# Board1.net
KiCad netlist of a schematic drawn in EAGLE
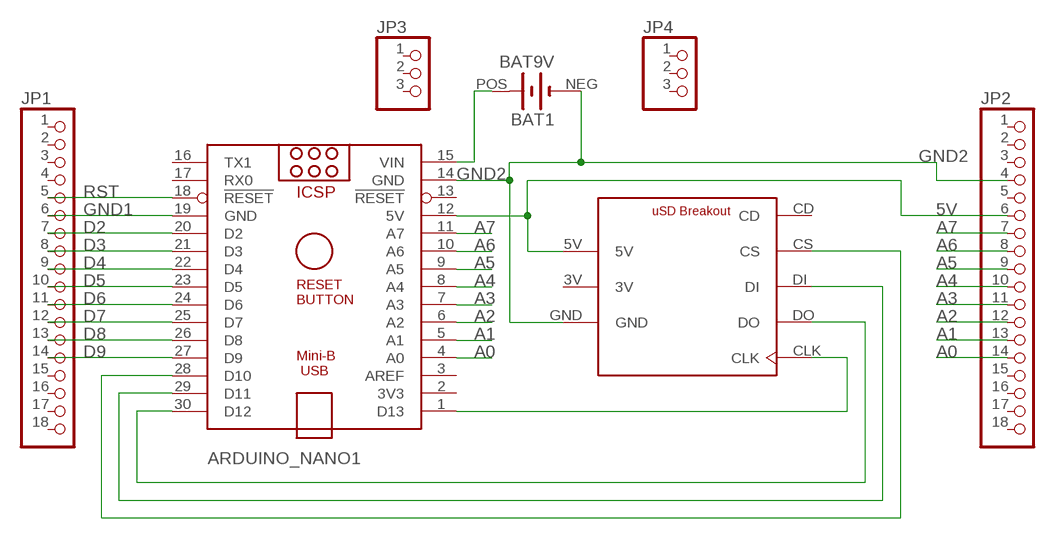
[diagram p0: schematic, sheet 1]

(export (version "E")
  (design (tool "Eeschema 10.0.6"))
  (components
    (comp (ref "ARDUINO_NANO1")
      (value "ARDUINO_NANO")
      (footprint "eagle-import:ARDUINO_NANO")
      (libsource (lib "eagle-import") (part "ARDUINO_NANO"))
    )
    (comp (ref "BAT1")
      (value "BAT9V")
      (footprint "eagle-import:BAT9V")
      (libsource (lib "eagle-import") (part "BAT9V"))
    )
    (comp (ref "JP1")
      (value "PINHD-1X18")
      (footprint "eagle-import:1X18")
      (libsource (lib "eagle-import") (part "PINHD-1X18"))
    )
    (comp (ref "JP2")
      (value "PINHD-1X18")
      (footprint "eagle-import:1X18")
      (libsource (lib "eagle-import") (part "PINHD-1X18"))
    )
    (comp (ref "JP3")
      (value "PINHD-1X3")
      (footprint "eagle-import:1X03")
      (libsource (lib "eagle-import") (part "PINHD-1X3"))
    )
    (comp (ref "JP4")
      (value "PINHD-1X3")
      (footprint "eagle-import:1X03")
      (libsource (lib "eagle-import") (part "PINHD-1X3"))
    )
    (comp (ref "USD1")
      (value "ADA254")
      (footprint "eagle-import:ADA254")
      (libsource (lib "eagle-import") (part "ADA254"))
    )
  )
  (nets
    (net (code "1") (name "/5V") (class "Default")
      (node (ref "ARDUINO_NANO1") (pin "12") (pinfunction "5V_12") (pintype "power_in"))
      (node (ref "JP2") (pin "6") (pinfunction "6_6") (pintype "passive"))
      (node (ref "USD1") (pin "5V") (pinfunction "5V_5V") (pintype "power_in"))
    )
    (net (code "2") (name "/A0") (class "Default")
      (node (ref "ARDUINO_NANO1") (pin "4") (pinfunction "A0_4") (pintype "bidirectional"))
      (node (ref "JP2") (pin "14") (pinfunction "14_14") (pintype "passive"))
    )
    (net (code "3") (name "/A1") (class "Default")
      (node (ref "ARDUINO_NANO1") (pin "5") (pinfunction "A1_5") (pintype "bidirectional"))
      (node (ref "JP2") (pin "13") (pinfunction "13_13") (pintype "passive"))
    )
    (net (code "4") (name "/A2") (class "Default")
      (node (ref "ARDUINO_NANO1") (pin "6") (pinfunction "A2_6") (pintype "bidirectional"))
      (node (ref "JP2") (pin "12") (pinfunction "12_12") (pintype "passive"))
    )
    (net (code "5") (name "/A3") (class "Default")
      (node (ref "ARDUINO_NANO1") (pin "7") (pinfunction "A3_7") (pintype "bidirectional"))
      (node (ref "JP2") (pin "11") (pinfunction "11_11") (pintype "passive"))
    )
    (net (code "6") (name "/A4") (class "Default")
      (node (ref "ARDUINO_NANO1") (pin "8") (pinfunction "A4_8") (pintype "bidirectional"))
      (node (ref "JP2") (pin "10") (pinfunction "10_10") (pintype "passive"))
    )
    (net (code "7") (name "/A5") (class "Default")
      (node (ref "ARDUINO_NANO1") (pin "9") (pinfunction "A5_9") (pintype "bidirectional"))
      (node (ref "JP2") (pin "9") (pinfunction "9_9") (pintype "passive"))
    )
    (net (code "8") (name "/A6") (class "Default")
      (node (ref "ARDUINO_NANO1") (pin "10") (pinfunction "A6_10") (pintype "bidirectional"))
      (node (ref "JP2") (pin "8") (pinfunction "8_8") (pintype "passive"))
    )
    (net (code "9") (name "/A7") (class "Default")
      (node (ref "ARDUINO_NANO1") (pin "11") (pinfunction "A7_11") (pintype "bidirectional"))
      (node (ref "JP2") (pin "7") (pinfunction "7_7") (pintype "passive"))
    )
    (net (code "10") (name "/D2") (class "Default")
      (node (ref "ARDUINO_NANO1") (pin "20") (pinfunction "D2_20") (pintype "bidirectional"))
      (node (ref "JP1") (pin "7") (pinfunction "7_7") (pintype "passive"))
    )
    (net (code "11") (name "/D3") (class "Default")
      (node (ref "ARDUINO_NANO1") (pin "21") (pinfunction "D3_21") (pintype "bidirectional"))
      (node (ref "JP1") (pin "8") (pinfunction "8_8") (pintype "passive"))
    )
    (net (code "12") (name "/D4") (class "Default")
      (node (ref "ARDUINO_NANO1") (pin "22") (pinfunction "D4_22") (pintype "bidirectional"))
      (node (ref "JP1") (pin "9") (pinfunction "9_9") (pintype "passive"))
    )
    (net (code "13") (name "/D5") (class "Default")
      (node (ref "ARDUINO_NANO1") (pin "23") (pinfunction "D5_23") (pintype "bidirectional"))
      (node (ref "JP1") (pin "10") (pinfunction "10_10") (pintype "passive"))
    )
    (net (code "14") (name "/D6") (class "Default")
      (node (ref "ARDUINO_NANO1") (pin "24") (pinfunction "D6_24") (pintype "bidirectional"))
      (node (ref "JP1") (pin "11") (pinfunction "11_11") (pintype "passive"))
    )
    (net (code "15") (name "/D7") (class "Default")
      (node (ref "ARDUINO_NANO1") (pin "25") (pinfunction "D7_25") (pintype "bidirectional"))
      (node (ref "JP1") (pin "12") (pinfunction "12_12") (pintype "passive"))
    )
    (net (code "16") (name "/D8") (class "Default")
      (node (ref "ARDUINO_NANO1") (pin "26") (pinfunction "D8_26") (pintype "bidirectional"))
      (node (ref "JP1") (pin "13") (pinfunction "13_13") (pintype "passive"))
    )
    (net (code "17") (name "/D9") (class "Default")
      (node (ref "ARDUINO_NANO1") (pin "27") (pinfunction "D9_27") (pintype "bidirectional"))
      (node (ref "JP1") (pin "14") (pinfunction "14_14") (pintype "passive"))
    )
    (net (code "18") (name "/GND1") (class "Default")
      (node (ref "ARDUINO_NANO1") (pin "19") (pinfunction "GND_19") (pintype "power_in"))
      (node (ref "JP1") (pin "6") (pinfunction "6_6") (pintype "passive"))
    )
    (net (code "19") (name "/GND2") (class "Default")
      (node (ref "ARDUINO_NANO1") (pin "14") (pinfunction "GND_14") (pintype "power_in"))
      (node (ref "BAT1") (pin "NEG") (pinfunction "-_NEG") (pintype "passive"))
      (node (ref "JP2") (pin "4") (pinfunction "4_4") (pintype "passive"))
      (node (ref "USD1") (pin "GND") (pinfunction "GND_GND") (pintype "power_in"))
    )
    (net (code "20") (name "/RST") (class "Default")
      (node (ref "ARDUINO_NANO1") (pin "18") (pinfunction "~{RESET}_18") (pintype "input"))
      (node (ref "JP1") (pin "5") (pinfunction "5_5") (pintype "passive"))
    )
    (net (code "21") (name "Net-(ARDUINO_NANO1-D10)") (class "Default")
      (node (ref "ARDUINO_NANO1") (pin "28") (pinfunction "D10_28") (pintype "bidirectional"))
      (node (ref "USD1") (pin "CS") (pinfunction "CS_CS") (pintype "input"))
    )
    (net (code "22") (name "Net-(ARDUINO_NANO1-D11)") (class "Default")
      (node (ref "ARDUINO_NANO1") (pin "29") (pinfunction "D11_29") (pintype "bidirectional"))
      (node (ref "USD1") (pin "DI") (pinfunction "DI_DI") (pintype "input"))
    )
    (net (code "23") (name "Net-(ARDUINO_NANO1-D12)") (class "Default")
      (node (ref "ARDUINO_NANO1") (pin "30") (pinfunction "D12_30") (pintype "bidirectional"))
      (node (ref "USD1") (pin "DO") (pinfunction "DO_DO") (pintype "output"))
    )
    (net (code "24") (name "Net-(ARDUINO_NANO1-D13)") (class "Default")
      (node (ref "ARDUINO_NANO1") (pin "1") (pinfunction "D13_1") (pintype "bidirectional"))
      (node (ref "USD1") (pin "CLK") (pinfunction "CLK_CLK") (pintype "bidirectional"))
    )
    (net (code "25") (name "Net-(ARDUINO_NANO1-VIN)") (class "Default")
      (node (ref "ARDUINO_NANO1") (pin "15") (pinfunction "VIN_15") (pintype "power_in"))
      (node (ref "BAT1") (pin "POS") (pinfunction "+_POS") (pintype "passive"))
    )
    (net (code "26") (name "unconnected-(ARDUINO_NANO1-3V3-Pad2)") (class "Default")
      (node (ref "ARDUINO_NANO1") (pin "2") (pinfunction "3V3_2") (pintype "output"))
    )
    (net (code "27") (name "unconnected-(ARDUINO_NANO1-AREF-Pad3)") (class "Default")
      (node (ref "ARDUINO_NANO1") (pin "3") (pinfunction "AREF_3") (pintype "input"))
    )
    (net (code "28") (name "unconnected-(ARDUINO_NANO1-RX0-Pad17)") (class "Default")
      (node (ref "ARDUINO_NANO1") (pin "17") (pinfunction "RX0_17") (pintype "bidirectional"))
    )
    (net (code "29") (name "unconnected-(ARDUINO_NANO1-TX1-Pad16)") (class "Default")
      (node (ref "ARDUINO_NANO1") (pin "16") (pinfunction "TX1_16") (pintype "bidirectional"))
    )
    (net (code "30") (name "unconnected-(ARDUINO_NANO1-~{RESET}-Pad13)") (class "Default")
      (node (ref "ARDUINO_NANO1") (pin "13") (pinfunction "~{RESET}_13") (pintype "input"))
    )
    (net (code "31") (name "unconnected-(JP1-Pad1)") (class "Default")
      (node (ref "JP1") (pin "1") (pinfunction "1_1") (pintype "passive"))
    )
    (net (code "32") (name "unconnected-(JP1-Pad2)") (class "Default")
      (node (ref "JP1") (pin "2") (pinfunction "2_2") (pintype "passive"))
    )
    (net (code "33") (name "unconnected-(JP1-Pad3)") (class "Default")
      (node (ref "JP1") (pin "3") (pinfunction "3_3") (pintype "passive"))
    )
    (net (code "34") (name "unconnected-(JP1-Pad4)") (class "Default")
      (node (ref "JP1") (pin "4") (pinfunction "4_4") (pintype "passive"))
    )
    (net (code "35") (name "unconnected-(JP1-Pad15)") (class "Default")
      (node (ref "JP1") (pin "15") (pinfunction "15_15") (pintype "passive"))
    )
    (net (code "36") (name "unconnected-(JP1-Pad16)") (class "Default")
      (node (ref "JP1") (pin "16") (pinfunction "16_16") (pintype "passive"))
    )
    (net (code "37") (name "unconnected-(JP1-Pad17)") (class "Default")
      (node (ref "JP1") (pin "17") (pinfunction "17_17") (pintype "passive"))
    )
    (net (code "38") (name "unconnected-(JP1-Pad18)") (class "Default")
      (node (ref "JP1") (pin "18") (pinfunction "18_18") (pintype "passive"))
    )
    (net (code "39") (name "unconnected-(JP2-Pad1)") (class "Default")
      (node (ref "JP2") (pin "1") (pinfunction "1_1") (pintype "passive"))
    )
    (net (code "40") (name "unconnected-(JP2-Pad2)") (class "Default")
      (node (ref "JP2") (pin "2") (pinfunction "2_2") (pintype "passive"))
    )
    (net (code "41") (name "unconnected-(JP2-Pad3)") (class "Default")
      (node (ref "JP2") (pin "3") (pinfunction "3_3") (pintype "passive"))
    )
    (net (code "42") (name "unconnected-(JP2-Pad5)") (class "Default")
      (node (ref "JP2") (pin "5") (pinfunction "5_5") (pintype "passive"))
    )
    (net (code "43") (name "unconnected-(JP2-Pad15)") (class "Default")
      (node (ref "JP2") (pin "15") (pinfunction "15_15") (pintype "passive"))
    )
    (net (code "44") (name "unconnected-(JP2-Pad16)") (class "Default")
      (node (ref "JP2") (pin "16") (pinfunction "16_16") (pintype "passive"))
    )
    (net (code "45") (name "unconnected-(JP2-Pad17)") (class "Default")
      (node (ref "JP2") (pin "17") (pinfunction "17_17") (pintype "passive"))
    )
    (net (code "46") (name "unconnected-(JP2-Pad18)") (class "Default")
      (node (ref "JP2") (pin "18") (pinfunction "18_18") (pintype "passive"))
    )
    (net (code "47") (name "unconnected-(JP3-Pad1)") (class "Default")
      (node (ref "JP3") (pin "1") (pinfunction "1_1") (pintype "passive"))
    )
    (net (code "48") (name "unconnected-(JP3-Pad2)") (class "Default")
      (node (ref "JP3") (pin "2") (pinfunction "2_2") (pintype "passive"))
    )
    (net (code "49") (name "unconnected-(JP3-Pad3)") (class "Default")
      (node (ref "JP3") (pin "3") (pinfunction "3_3") (pintype "passive"))
    )
    (net (code "50") (name "unconnected-(JP4-Pad1)") (class "Default")
      (node (ref "JP4") (pin "1") (pinfunction "1_1") (pintype "passive"))
    )
    (net (code "51") (name "unconnected-(JP4-Pad2)") (class "Default")
      (node (ref "JP4") (pin "2") (pinfunction "2_2") (pintype "passive"))
    )
    (net (code "52") (name "unconnected-(JP4-Pad3)") (class "Default")
      (node (ref "JP4") (pin "3") (pinfunction "3_3") (pintype "passive"))
    )
    (net (code "53") (name "unconnected-(USD1-Pad3V)") (class "Default")
      (node (ref "USD1") (pin "3V") (pinfunction "3V_3V") (pintype "output"))
    )
    (net (code "54") (name "unconnected-(USD1-PadCD)") (class "Default")
      (node (ref "USD1") (pin "CD") (pinfunction "CD_CD") (pintype "bidirectional"))
    )
  )
)
